# OpenSegment.net
KiCad netlist of a schematic drawn in EAGLE
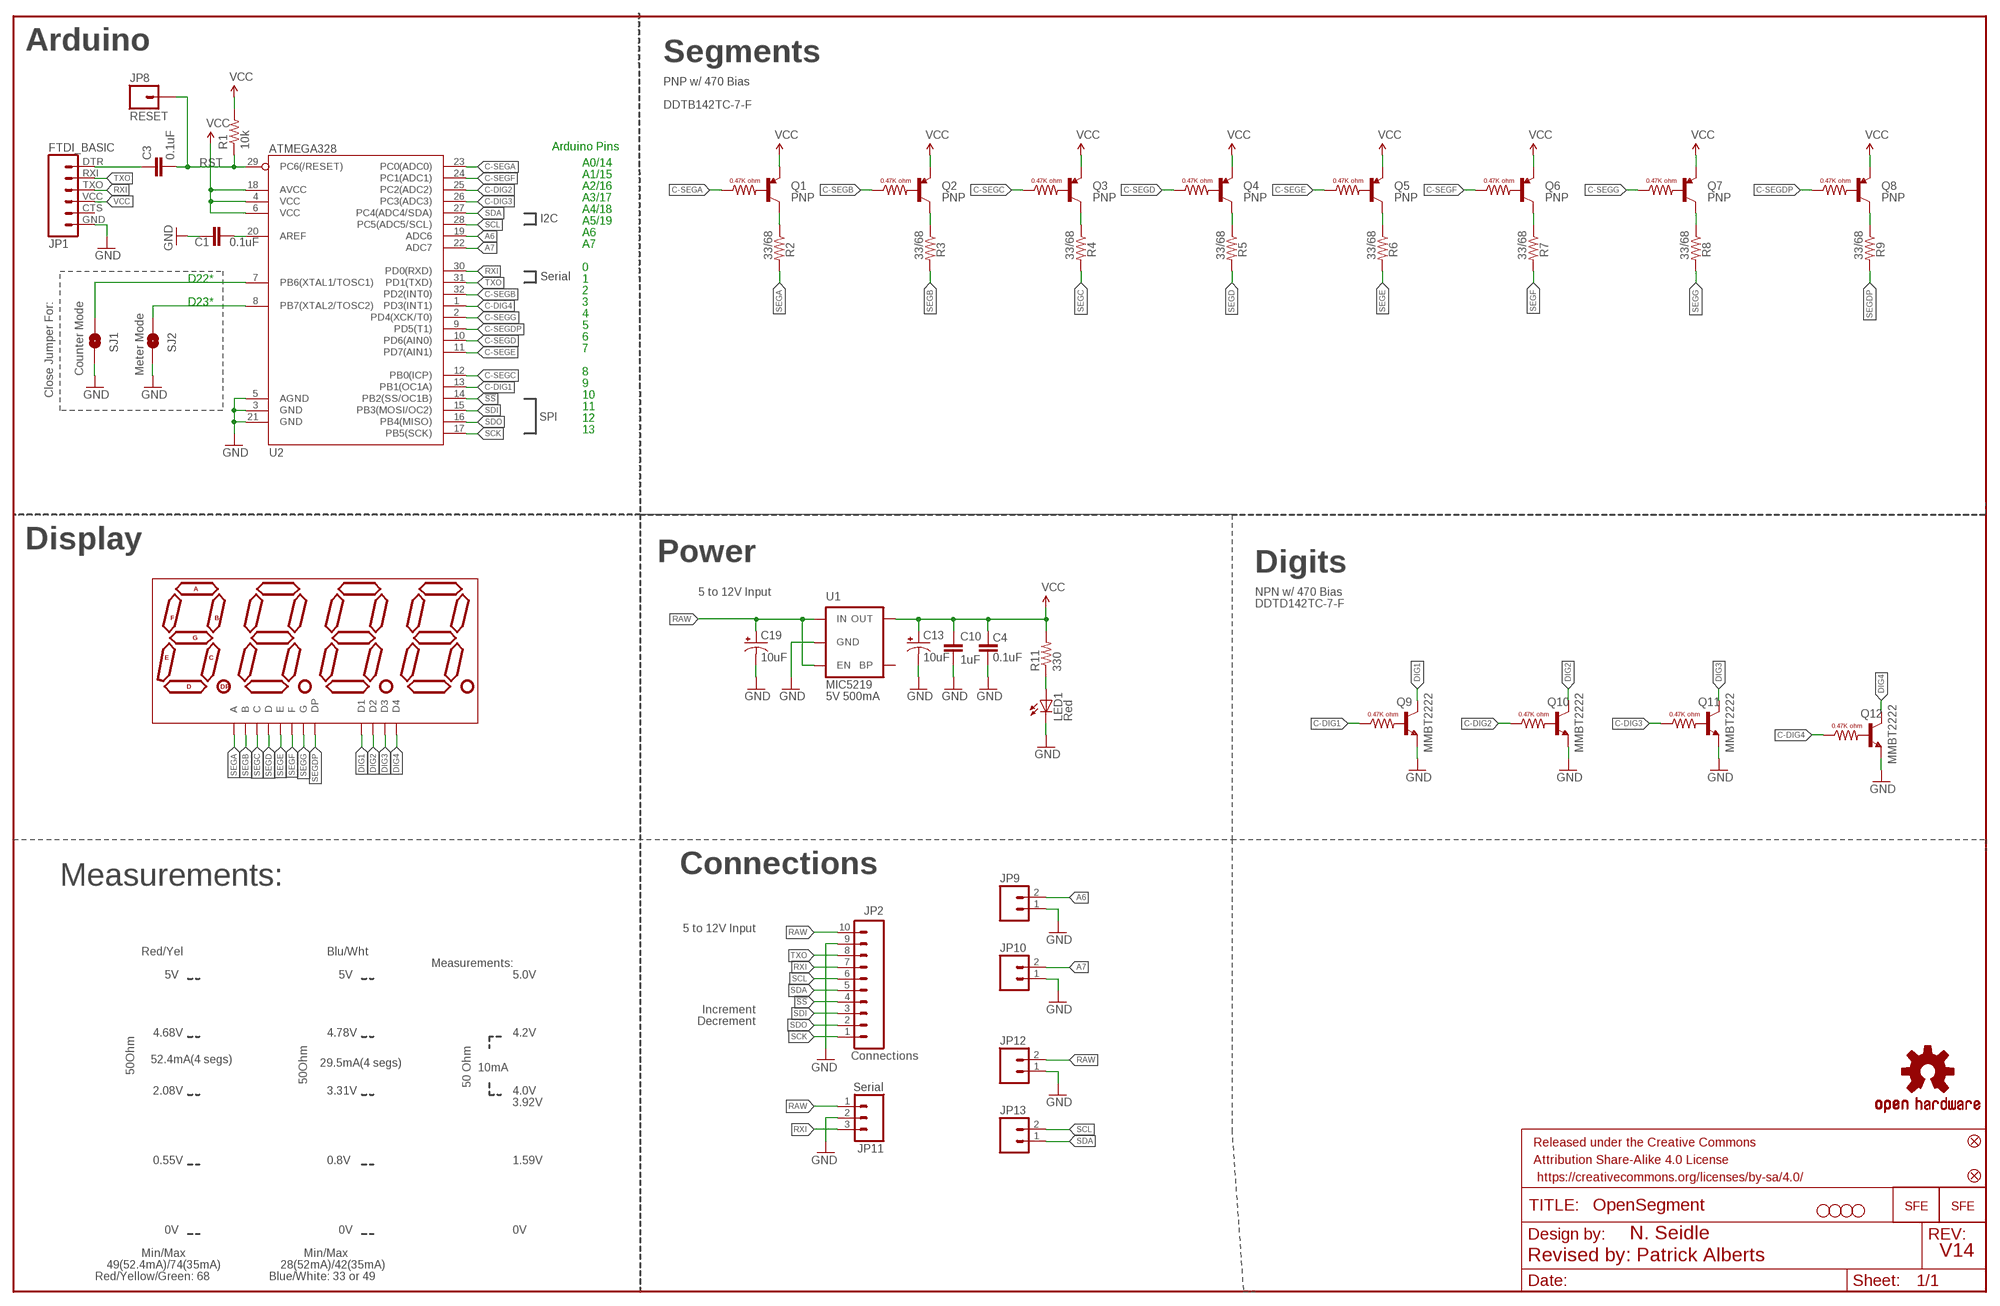
[diagram p0: schematic, sheet 1]

(export (version "E")
  (design (tool "Eeschema 10.0.6"))
  (components
    (comp (ref "C1")
      (value "0.1uF")
      (footprint "eagle-import:0603-CAP")
      (libsource (lib "eagle-import") (part "0.1UF-25V(+80/-20%)(0603)"))
    )
    (comp (ref "C3")
      (value "0.1uF")
      (footprint "eagle-import:0603-CAP")
      (libsource (lib "eagle-import") (part "0.1UF-25V(+80/-20%)(0603)"))
    )
    (comp (ref "C4")
      (value "0.1uF")
      (footprint "eagle-import:0603-CAP")
      (libsource (lib "eagle-import") (part "0.1UF-25V(+80/-20%)(0603)"))
    )
    (comp (ref "C10")
      (value "1uF")
      (footprint "eagle-import:0603-CAP")
      (libsource (lib "eagle-import") (part "1.0UF-16V-10%(0603)"))
    )
    (comp (ref "C13")
      (value "10uF")
      (footprint "eagle-import:EIA3216")
      (libsource (lib "eagle-import") (part "CAP_POL1206"))
    )
    (comp (ref "C19")
      (value "10uF")
      (footprint "eagle-import:EIA3216")
      (libsource (lib "eagle-import") (part "CAP_POL1206"))
    )
    (comp (ref "FID1")
      (value "FIDUCIAL1X2")
      (footprint "eagle-import:FIDUCIAL-1X2")
      (libsource (lib "eagle-import") (part "FIDUCIAL1X2"))
    )
    (comp (ref "FID2")
      (value "FIDUCIAL1X2")
      (footprint "eagle-import:FIDUCIAL-1X2")
      (libsource (lib "eagle-import") (part "FIDUCIAL1X2"))
    )
    (comp (ref "FRAME1")
      (value "FRAME-LEDGER")
      (footprint "eagle-import:CREATIVE_COMMONS")
      (libsource (lib "eagle-import") (part "FRAME-LEDGER"))
    )
    (comp (ref "JP1")
      (value "FTDI_BASIC")
      (footprint "eagle-import:FTDI_BASIC")
      (libsource (lib "eagle-import") (part "FTDI_BASICPTH"))
    )
    (comp (ref "JP2")
      (value "Connections")
      (footprint "eagle-import:1X10")
      (libsource (lib "eagle-import") (part "M10{dblquote}"))
    )
    (comp (ref "JP3")
      (value "STAND-OFF")
      (footprint "eagle-import:STAND-OFF")
      (libsource (lib "eagle-import") (part "STAND-OFF"))
    )
    (comp (ref "JP4")
      (value "STAND-OFF")
      (footprint "eagle-import:STAND-OFF")
      (libsource (lib "eagle-import") (part "STAND-OFF"))
    )
    (comp (ref "JP5")
      (value "STAND-OFF")
      (footprint "eagle-import:STAND-OFF")
      (libsource (lib "eagle-import") (part "STAND-OFF"))
    )
    (comp (ref "JP6")
      (value "STAND-OFF")
      (footprint "eagle-import:STAND-OFF")
      (libsource (lib "eagle-import") (part "STAND-OFF"))
    )
    (comp (ref "JP8")
      (value "RESET")
      (footprint "eagle-import:1X01")
      (libsource (lib "eagle-import") (part "M01PTH"))
    )
    (comp (ref "JP9")
      (value "M02PTH")
      (footprint "eagle-import:1X02")
      (libsource (lib "eagle-import") (part "M02PTH"))
    )
    (comp (ref "JP10")
      (value "M02PTH")
      (footprint "eagle-import:1X02")
      (libsource (lib "eagle-import") (part "M02PTH"))
    )
    (comp (ref "JP11")
      (value "Serial")
      (footprint "eagle-import:JST-3-PTH")
      (libsource (lib "eagle-import") (part "M03JST-PTH"))
    )
    (comp (ref "JP12")
      (value "M02PTH")
      (footprint "eagle-import:1X02")
      (libsource (lib "eagle-import") (part "M02PTH"))
    )
    (comp (ref "JP13")
      (value "M02PTH")
      (footprint "eagle-import:1X02")
      (libsource (lib "eagle-import") (part "M02PTH"))
    )
    (comp (ref "LED1")
      (value "Red")
      (footprint "eagle-import:LED-0603")
      (libsource (lib "eagle-import") (part "LED-RED0603"))
    )
    (comp (ref "Q1")
      (value "PNP")
      (footprint "eagle-import:SOT23-3")
      (libsource (lib "eagle-import") (part "TRANSISTOR-PNP-DDTB142TC"))
    )
    (comp (ref "Q2")
      (value "PNP")
      (footprint "eagle-import:SOT23-3")
      (libsource (lib "eagle-import") (part "TRANSISTOR-PNP-DDTB142TC"))
    )
    (comp (ref "Q3")
      (value "PNP")
      (footprint "eagle-import:SOT23-3")
      (libsource (lib "eagle-import") (part "TRANSISTOR-PNP-DDTB142TC"))
    )
    (comp (ref "Q4")
      (value "PNP")
      (footprint "eagle-import:SOT23-3")
      (libsource (lib "eagle-import") (part "TRANSISTOR-PNP-DDTB142TC"))
    )
    (comp (ref "Q5")
      (value "PNP")
      (footprint "eagle-import:SOT23-3")
      (libsource (lib "eagle-import") (part "TRANSISTOR-PNP-DDTB142TC"))
    )
    (comp (ref "Q6")
      (value "PNP")
      (footprint "eagle-import:SOT23-3")
      (libsource (lib "eagle-import") (part "TRANSISTOR-PNP-DDTB142TC"))
    )
    (comp (ref "Q7")
      (value "PNP")
      (footprint "eagle-import:SOT23-3")
      (libsource (lib "eagle-import") (part "TRANSISTOR-PNP-DDTB142TC"))
    )
    (comp (ref "Q8")
      (value "PNP")
      (footprint "eagle-import:SOT23-3")
      (libsource (lib "eagle-import") (part "TRANSISTOR-PNP-DDTB142TC"))
    )
    (comp (ref "Q9")
      (value "MMBT2222")
      (footprint "eagle-import:SOT23-3")
      (libsource (lib "eagle-import") (part "TRANSISTOR-NPN-DDTD142TC"))
    )
    (comp (ref "Q10")
      (value "MMBT2222")
      (footprint "eagle-import:SOT23-3")
      (libsource (lib "eagle-import") (part "TRANSISTOR-NPN-DDTD142TC"))
    )
    (comp (ref "Q11")
      (value "MMBT2222")
      (footprint "eagle-import:SOT23-3")
      (libsource (lib "eagle-import") (part "TRANSISTOR-NPN-DDTD142TC"))
    )
    (comp (ref "Q12")
      (value "MMBT2222")
      (footprint "eagle-import:SOT23-3")
      (libsource (lib "eagle-import") (part "TRANSISTOR-NPN-DDTD142TC"))
    )
    (comp (ref "R1")
      (value "10k")
      (footprint "eagle-import:0603-RES")
      (libsource (lib "eagle-import") (part "10KOHM1/10W1%(0603)0603"))
    )
    (comp (ref "R2")
      (value "33/68")
      (footprint "eagle-import:0603")
      (libsource (lib "eagle-import") (part "33OHM1/10W1%(0603)"))
    )
    (comp (ref "R3")
      (value "33/68")
      (footprint "eagle-import:0603")
      (libsource (lib "eagle-import") (part "33OHM1/10W1%(0603)"))
    )
    (comp (ref "R4")
      (value "33/68")
      (footprint "eagle-import:0603")
      (libsource (lib "eagle-import") (part "33OHM1/10W1%(0603)"))
    )
    (comp (ref "R5")
      (value "33/68")
      (footprint "eagle-import:0603")
      (libsource (lib "eagle-import") (part "33OHM1/10W1%(0603)"))
    )
    (comp (ref "R6")
      (value "33/68")
      (footprint "eagle-import:0603")
      (libsource (lib "eagle-import") (part "33OHM1/10W1%(0603)"))
    )
    (comp (ref "R7")
      (value "33/68")
      (footprint "eagle-import:0603")
      (libsource (lib "eagle-import") (part "33OHM1/10W1%(0603)"))
    )
    (comp (ref "R8")
      (value "33/68")
      (footprint "eagle-import:0603")
      (libsource (lib "eagle-import") (part "33OHM1/10W1%(0603)"))
    )
    (comp (ref "R9")
      (value "33/68")
      (footprint "eagle-import:0603")
      (libsource (lib "eagle-import") (part "33OHM1/10W1%(0603)"))
    )
    (comp (ref "R11")
      (value "330")
      (footprint "eagle-import:0603-RES")
      (libsource (lib "eagle-import") (part "330OHM1/10W1%(0603)"))
    )
    (comp (ref "SJ1")
      (value "Counter Ctl")
      (footprint "eagle-import:SJ_2S-NO")
      (libsource (lib "eagle-import") (part "SOLDERJUMPERNO"))
    )
    (comp (ref "SJ2")
      (value "Counter Ctl")
      (footprint "eagle-import:SJ_2S-NO")
      (libsource (lib "eagle-import") (part "SOLDERJUMPERNO"))
    )
    (comp (ref "U$2")
      (value "LOGO-SFESK")
      (footprint "eagle-import:SFE-LOGO-FLAME")
      (libsource (lib "eagle-import") (part "LOGO-SFESK"))
    )
    (comp (ref "U$4")
      (value "OSHW-LOGOS")
      (footprint "eagle-import:OSHW-LOGO-S")
      (libsource (lib "eagle-import") (part "OSHW-LOGOS"))
    )
    (comp (ref "U$7")
      (value "LOGO-SFENW2")
      (footprint "eagle-import:SFE-NEW-WEB")
      (libsource (lib "eagle-import") (part "LOGO-SFENW2"))
    )
    (comp (ref "U1")
      (value "MIC5219")
      (footprint "eagle-import:SOT23-5")
      (libsource (lib "eagle-import") (part "V_REG_LDOSMD"))
    )
    (comp (ref "U2")
      (value "ATMEGA328")
      (footprint "eagle-import:TQFP32-08")
      (libsource (lib "eagle-import") (part "ATMEGA168"))
    )
    (comp (ref "U3")
      (value "7-SEGMENT-4DIGIT-COUNTERPTH")
      (footprint "eagle-import:7-SEGMENT-4DIGIT-COUNTER")
      (libsource (lib "eagle-import") (part "7-SEGMENT-4DIGIT-COUNTERPTH"))
    )
  )
  (nets
    (net (code "1") (name "/RST") (class "Default")
      (node (ref "C3") (pin "2") (pinfunction "2_2") (pintype "passive"))
      (node (ref "JP8") (pin "1") (pinfunction "1_1") (pintype "passive"))
      (node (ref "R1") (pin "1") (pinfunction "1_1") (pintype "passive"))
      (node (ref "U2") (pin "29") (pinfunction "PC6(/RESET)_29") (pintype "bidirectional"))
    )
    (net (code "2") (name "/~{SS}") (class "Default")
      (node (ref "JP2") (pin "4") (pinfunction "4_4") (pintype "passive"))
      (node (ref "U2") (pin "14") (pinfunction "PB2(SS/OC1B)_14") (pintype "bidirectional"))
    )
    (net (code "3") (name "A6") (class "Default")
      (node (ref "JP9") (pin "2") (pinfunction "2_2") (pintype "passive"))
      (node (ref "U2") (pin "19") (pinfunction "ADC6_19") (pintype "bidirectional"))
    )
    (net (code "4") (name "A7") (class "Default")
      (node (ref "JP10") (pin "2") (pinfunction "2_2") (pintype "passive"))
      (node (ref "U2") (pin "22") (pinfunction "ADC7_22") (pintype "bidirectional"))
    )
    (net (code "5") (name "C-DIG1") (class "Default")
      (node (ref "Q9") (pin "1") (pinfunction "B_1") (pintype "passive"))
      (node (ref "U2") (pin "13") (pinfunction "PB1(OC1A)_13") (pintype "bidirectional"))
    )
    (net (code "6") (name "C-DIG2") (class "Default")
      (node (ref "Q10") (pin "1") (pinfunction "B_1") (pintype "passive"))
      (node (ref "U2") (pin "25") (pinfunction "PC2(ADC2)_25") (pintype "bidirectional"))
    )
    (net (code "7") (name "C-DIG3") (class "Default")
      (node (ref "Q11") (pin "1") (pinfunction "B_1") (pintype "passive"))
      (node (ref "U2") (pin "26") (pinfunction "PC3(ADC3)_26") (pintype "bidirectional"))
    )
    (net (code "8") (name "C-DIG4") (class "Default")
      (node (ref "Q12") (pin "1") (pinfunction "B_1") (pintype "passive"))
      (node (ref "U2") (pin "1") (pinfunction "PD3(INT1)_1") (pintype "bidirectional"))
    )
    (net (code "9") (name "C-SEGA") (class "Default")
      (node (ref "Q1") (pin "1") (pinfunction "B_1") (pintype "passive"))
      (node (ref "U2") (pin "23") (pinfunction "PC0(ADC0)_23") (pintype "bidirectional"))
    )
    (net (code "10") (name "C-SEGB") (class "Default")
      (node (ref "Q2") (pin "1") (pinfunction "B_1") (pintype "passive"))
      (node (ref "U2") (pin "32") (pinfunction "PD2(INT0)_32") (pintype "bidirectional"))
    )
    (net (code "11") (name "C-SEGC") (class "Default")
      (node (ref "Q3") (pin "1") (pinfunction "B_1") (pintype "passive"))
      (node (ref "U2") (pin "12") (pinfunction "PB0(ICP)_12") (pintype "bidirectional"))
    )
    (net (code "12") (name "C-SEGD") (class "Default")
      (node (ref "Q4") (pin "1") (pinfunction "B_1") (pintype "passive"))
      (node (ref "U2") (pin "10") (pinfunction "PD6(AIN0)_10") (pintype "bidirectional"))
    )
    (net (code "13") (name "C-SEGDP") (class "Default")
      (node (ref "Q8") (pin "1") (pinfunction "B_1") (pintype "passive"))
      (node (ref "U2") (pin "9") (pinfunction "PD5(T1)_9") (pintype "bidirectional"))
    )
    (net (code "14") (name "C-SEGE") (class "Default")
      (node (ref "Q5") (pin "1") (pinfunction "B_1") (pintype "passive"))
      (node (ref "U2") (pin "11") (pinfunction "PD7(AIN1)_11") (pintype "bidirectional"))
    )
    (net (code "15") (name "C-SEGF") (class "Default")
      (node (ref "Q6") (pin "1") (pinfunction "B_1") (pintype "passive"))
      (node (ref "U2") (pin "24") (pinfunction "PC1(ADC1)_24") (pintype "bidirectional"))
    )
    (net (code "16") (name "C-SEGG") (class "Default")
      (node (ref "Q7") (pin "1") (pinfunction "B_1") (pintype "passive"))
      (node (ref "U2") (pin "2") (pinfunction "PD4(XCK/T0)_2") (pintype "bidirectional"))
    )
    (net (code "17") (name "DIG1") (class "Default")
      (node (ref "Q9") (pin "3") (pinfunction "C_3") (pintype "passive"))
      (node (ref "U3") (pin "12") (pinfunction "D1_12") (pintype "bidirectional"))
    )
    (net (code "18") (name "DIG2") (class "Default")
      (node (ref "Q10") (pin "3") (pinfunction "C_3") (pintype "passive"))
      (node (ref "U3") (pin "9") (pinfunction "D2_9") (pintype "bidirectional"))
    )
    (net (code "19") (name "DIG3") (class "Default")
      (node (ref "Q11") (pin "3") (pinfunction "C_3") (pintype "passive"))
      (node (ref "U3") (pin "8") (pinfunction "D3_8") (pintype "bidirectional"))
    )
    (net (code "20") (name "DIG4") (class "Default")
      (node (ref "Q12") (pin "3") (pinfunction "C_3") (pintype "passive"))
      (node (ref "U3") (pin "6") (pinfunction "D4_6") (pintype "bidirectional"))
    )
    (net (code "21") (name "GND") (class "Default")
      (node (ref "C1") (pin "1") (pinfunction "1_1") (pintype "passive"))
      (node (ref "C10") (pin "2") (pinfunction "2_2") (pintype "passive"))
      (node (ref "C13") (pin "C") (pinfunction "-_C") (pintype "passive"))
      (node (ref "C19") (pin "C") (pinfunction "-_C") (pintype "passive"))
      (node (ref "C4") (pin "1") (pinfunction "1_1") (pintype "passive"))
      (node (ref "JP1") (pin "GND") (pinfunction "6_GND") (pintype "passive"))
      (node (ref "JP10") (pin "1") (pinfunction "1_1") (pintype "passive"))
      (node (ref "JP11") (pin "2") (pinfunction "2_2") (pintype "passive"))
      (node (ref "JP12") (pin "1") (pinfunction "1_1") (pintype "passive"))
      (node (ref "JP2") (pin "9") (pinfunction "9_9") (pintype "passive"))
      (node (ref "JP9") (pin "1") (pinfunction "1_1") (pintype "passive"))
      (node (ref "LED1") (pin "C") (pinfunction "C_C") (pintype "passive"))
      (node (ref "Q10") (pin "2") (pinfunction "E_2") (pintype "passive"))
      (node (ref "Q11") (pin "2") (pinfunction "E_2") (pintype "passive"))
      (node (ref "Q12") (pin "2") (pinfunction "E_2") (pintype "passive"))
      (node (ref "Q9") (pin "2") (pinfunction "E_2") (pintype "passive"))
      (node (ref "SJ1") (pin "2") (pinfunction "2_2") (pintype "passive"))
      (node (ref "SJ2") (pin "2") (pinfunction "2_2") (pintype "passive"))
      (node (ref "U1") (pin "2") (pinfunction "GND_2") (pintype "input"))
      (node (ref "U2") (pin "21") (pinfunction "GND_21") (pintype "bidirectional"))
      (node (ref "U2") (pin "3") (pinfunction "GND_3") (pintype "bidirectional"))
      (node (ref "U2") (pin "5") (pinfunction "AGND_5") (pintype "bidirectional"))
    )
    (net (code "22") (name "Net-(JP1-1)") (class "Default")
      (node (ref "C3") (pin "1") (pinfunction "1_1") (pintype "passive"))
      (node (ref "JP1") (pin "DTR") (pinfunction "1_DTR") (pintype "passive"))
    )
    (net (code "23") (name "Net-(LED1-PadA)") (class "Default")
      (node (ref "LED1") (pin "A") (pinfunction "A_A") (pintype "passive"))
      (node (ref "R11") (pin "1") (pinfunction "1_1") (pintype "passive"))
    )
    (net (code "24") (name "Net-(Q1-C)") (class "Default")
      (node (ref "Q1") (pin "3") (pinfunction "C_3") (pintype "passive"))
      (node (ref "R2") (pin "1") (pinfunction "1_1") (pintype "passive"))
    )
    (net (code "25") (name "Net-(Q2-C)") (class "Default")
      (node (ref "Q2") (pin "3") (pinfunction "C_3") (pintype "passive"))
      (node (ref "R3") (pin "1") (pinfunction "1_1") (pintype "passive"))
    )
    (net (code "26") (name "Net-(Q3-C)") (class "Default")
      (node (ref "Q3") (pin "3") (pinfunction "C_3") (pintype "passive"))
      (node (ref "R4") (pin "1") (pinfunction "1_1") (pintype "passive"))
    )
    (net (code "27") (name "Net-(Q4-C)") (class "Default")
      (node (ref "Q4") (pin "3") (pinfunction "C_3") (pintype "passive"))
      (node (ref "R5") (pin "1") (pinfunction "1_1") (pintype "passive"))
    )
    (net (code "28") (name "Net-(Q5-C)") (class "Default")
      (node (ref "Q5") (pin "3") (pinfunction "C_3") (pintype "passive"))
      (node (ref "R6") (pin "1") (pinfunction "1_1") (pintype "passive"))
    )
    (net (code "29") (name "Net-(Q6-C)") (class "Default")
      (node (ref "Q6") (pin "3") (pinfunction "C_3") (pintype "passive"))
      (node (ref "R7") (pin "1") (pinfunction "1_1") (pintype "passive"))
    )
    (net (code "30") (name "Net-(Q7-C)") (class "Default")
      (node (ref "Q7") (pin "3") (pinfunction "C_3") (pintype "passive"))
      (node (ref "R8") (pin "1") (pinfunction "1_1") (pintype "passive"))
    )
    (net (code "31") (name "Net-(Q8-C)") (class "Default")
      (node (ref "Q8") (pin "3") (pinfunction "C_3") (pintype "passive"))
      (node (ref "R9") (pin "1") (pinfunction "1_1") (pintype "passive"))
    )
    (net (code "32") (name "Net-(U2-AREF)") (class "Default")
      (node (ref "C1") (pin "2") (pinfunction "2_2") (pintype "passive"))
      (node (ref "U2") (pin "20") (pinfunction "AREF_20") (pintype "bidirectional"))
    )
    (net (code "33") (name "Net-(U2-PB6(XTAL1{slash}TOSC1))") (class "Default")
      (node (ref "SJ1") (pin "1") (pinfunction "1_1") (pintype "passive"))
      (node (ref "U2") (pin "7") (pinfunction "PB6(XTAL1/TOSC1)_7") (pintype "bidirectional"))
    )
    (net (code "34") (name "Net-(U2-PB7(XTAL2{slash}TOSC2))") (class "Default")
      (node (ref "SJ2") (pin "1") (pinfunction "1_1") (pintype "passive"))
      (node (ref "U2") (pin "8") (pinfunction "PB7(XTAL2/TOSC2)_8") (pintype "bidirectional"))
    )
    (net (code "35") (name "RAW") (class "Default")
      (node (ref "C19") (pin "A") (pinfunction "+_A") (pintype "passive"))
      (node (ref "JP11") (pin "1") (pinfunction "1_1") (pintype "passive"))
      (node (ref "JP12") (pin "2") (pinfunction "2_2") (pintype "passive"))
      (node (ref "JP2") (pin "10") (pinfunction "10_10") (pintype "passive"))
      (node (ref "U1") (pin "1") (pinfunction "IN_1") (pintype "input"))
      (node (ref "U1") (pin "3") (pinfunction "EN_3") (pintype "input"))
    )
    (net (code "36") (name "RXI") (class "Default")
      (node (ref "JP1") (pin "TXO") (pinfunction "3_TXO") (pintype "passive"))
      (node (ref "JP11") (pin "3") (pinfunction "3_3") (pintype "passive"))
      (node (ref "JP2") (pin "7") (pinfunction "7_7") (pintype "passive"))
      (node (ref "U2") (pin "30") (pinfunction "PD0(RXD)_30") (pintype "bidirectional"))
    )
    (net (code "37") (name "SCK") (class "Default")
      (node (ref "JP2") (pin "1") (pinfunction "1_1") (pintype "passive"))
      (node (ref "U2") (pin "17") (pinfunction "PB5(SCK)_17") (pintype "bidirectional"))
    )
    (net (code "38") (name "SCL") (class "Default")
      (node (ref "JP13") (pin "2") (pinfunction "2_2") (pintype "passive"))
      (node (ref "JP2") (pin "6") (pinfunction "6_6") (pintype "passive"))
      (node (ref "U2") (pin "28") (pinfunction "PC5(ADC5/SCL)_28") (pintype "bidirectional"))
    )
    (net (code "39") (name "SDA") (class "Default")
      (node (ref "JP13") (pin "1") (pinfunction "1_1") (pintype "passive"))
      (node (ref "JP2") (pin "5") (pinfunction "5_5") (pintype "passive"))
      (node (ref "U2") (pin "27") (pinfunction "PC4(ADC4/SDA)_27") (pintype "bidirectional"))
    )
    (net (code "40") (name "SDI") (class "Default")
      (node (ref "JP2") (pin "3") (pinfunction "3_3") (pintype "passive"))
      (node (ref "U2") (pin "15") (pinfunction "PB3(MOSI/OC2)_15") (pintype "bidirectional"))
    )
    (net (code "41") (name "SDO") (class "Default")
      (node (ref "JP2") (pin "2") (pinfunction "2_2") (pintype "passive"))
      (node (ref "U2") (pin "16") (pinfunction "PB4(MISO)_16") (pintype "bidirectional"))
    )
    (net (code "42") (name "SEGA") (class "Default")
      (node (ref "R2") (pin "2") (pinfunction "2_2") (pintype "passive"))
      (node (ref "U3") (pin "11") (pinfunction "A_11") (pintype "bidirectional"))
    )
    (net (code "43") (name "SEGB") (class "Default")
      (node (ref "R3") (pin "2") (pinfunction "2_2") (pintype "passive"))
      (node (ref "U3") (pin "7") (pinfunction "B_7") (pintype "bidirectional"))
    )
    (net (code "44") (name "SEGC") (class "Default")
      (node (ref "R4") (pin "2") (pinfunction "2_2") (pintype "passive"))
      (node (ref "U3") (pin "4") (pinfunction "C_4") (pintype "bidirectional"))
    )
    (net (code "45") (name "SEGD") (class "Default")
      (node (ref "R5") (pin "2") (pinfunction "2_2") (pintype "passive"))
      (node (ref "U3") (pin "2") (pinfunction "D_2") (pintype "bidirectional"))
    )
    (net (code "46") (name "SEGDP") (class "Default")
      (node (ref "R9") (pin "2") (pinfunction "2_2") (pintype "passive"))
      (node (ref "U3") (pin "3") (pinfunction "DP_3") (pintype "bidirectional"))
    )
    (net (code "47") (name "SEGE") (class "Default")
      (node (ref "R6") (pin "2") (pinfunction "2_2") (pintype "passive"))
      (node (ref "U3") (pin "1") (pinfunction "E_1") (pintype "bidirectional"))
    )
    (net (code "48") (name "SEGF") (class "Default")
      (node (ref "R7") (pin "2") (pinfunction "2_2") (pintype "passive"))
      (node (ref "U3") (pin "10") (pinfunction "F_10") (pintype "bidirectional"))
    )
    (net (code "49") (name "SEGG") (class "Default")
      (node (ref "R8") (pin "2") (pinfunction "2_2") (pintype "passive"))
      (node (ref "U3") (pin "5") (pinfunction "G_5") (pintype "bidirectional"))
    )
    (net (code "50") (name "TXO") (class "Default")
      (node (ref "JP1") (pin "RXI") (pinfunction "2_RXI") (pintype "passive"))
      (node (ref "JP2") (pin "8") (pinfunction "8_8") (pintype "passive"))
      (node (ref "U2") (pin "31") (pinfunction "PD1(TXD)_31") (pintype "bidirectional"))
    )
    (net (code "51") (name "VCC") (class "Default")
      (node (ref "C10") (pin "1") (pinfunction "1_1") (pintype "passive"))
      (node (ref "C13") (pin "A") (pinfunction "+_A") (pintype "passive"))
      (node (ref "C4") (pin "2") (pinfunction "2_2") (pintype "passive"))
      (node (ref "JP1") (pin "VCC") (pinfunction "4_VCC") (pintype "passive"))
      (node (ref "Q1") (pin "2") (pinfunction "E_2") (pintype "passive"))
      (node (ref "Q2") (pin "2") (pinfunction "E_2") (pintype "passive"))
      (node (ref "Q3") (pin "2") (pinfunction "E_2") (pintype "passive"))
      (node (ref "Q4") (pin "2") (pinfunction "E_2") (pintype "passive"))
      (node (ref "Q5") (pin "2") (pinfunction "E_2") (pintype "passive"))
      (node (ref "Q6") (pin "2") (pinfunction "E_2") (pintype "passive"))
      (node (ref "Q7") (pin "2") (pinfunction "E_2") (pintype "passive"))
      (node (ref "Q8") (pin "2") (pinfunction "E_2") (pintype "passive"))
      (node (ref "R1") (pin "2") (pinfunction "2_2") (pintype "passive"))
      (node (ref "R11") (pin "2") (pinfunction "2_2") (pintype "passive"))
      (node (ref "U1") (pin "5") (pinfunction "OUT_5") (pintype "passive"))
      (node (ref "U2") (pin "18") (pinfunction "AVCC_18") (pintype "bidirectional"))
      (node (ref "U2") (pin "4") (pinfunction "VCC_4") (pintype "bidirectional"))
      (node (ref "U2") (pin "6") (pinfunction "VCC_6") (pintype "bidirectional"))
    )
    (net (code "52") (name "unconnected-(JP1-5-PadCTS)") (class "Default")
      (node (ref "JP1") (pin "CTS") (pinfunction "5_CTS") (pintype "passive"))
    )
    (net (code "53") (name "unconnected-(U1-BP-Pad4)") (class "Default")
      (node (ref "U1") (pin "4") (pinfunction "BP_4") (pintype "input"))
    )
  )
)
